# Single-ADC_ADS1252U.net
KiCad netlist of a schematic drawn in Altium Designer
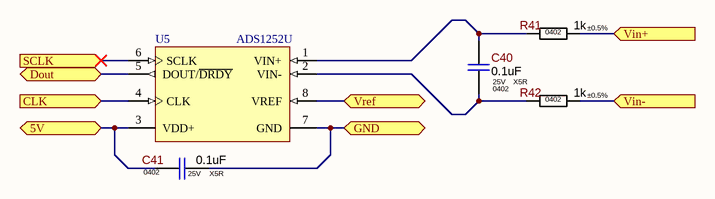
[diagram p0: Single-ADC_ADS1252U.SchDoc]

(export (version "E")
  (design (tool "Eeschema 10.0.6"))
  (components
    (comp (ref "C40")
      (value "0.1uF")
      (footprint "C_CERAMIC_0402_MED")
      (description "100nF 25V X5R ±10% 0402 Ceramic Capacitor RoHS")
      (fields
        (field (name "PART NUMBER") "CL05A104KA5NNNC")
        (field (name "MANUFACTURER") "Samsung Electro-Mechanics")
        (field (name "PACKAGE") "0402")
        (field (name "VOLTAGE") "25V")
        (field (name "DIELECTRIC TYPE") "X5R")
      )
      (libsource (lib "EL.XXX.T01") (part "CL05A104KA5NNNC"))
    )
    (comp (ref "C41")
      (value "0.1uF")
      (footprint "C_CERAMIC_0402_HI")
      (description "100nF 25V X5R ±10% 0402 Ceramic Capacitor RoHS")
      (fields
        (field (name "PACKAGE") "0402")
        (field (name "VOLTAGE") "25V")
        (field (name "DIELECTRIC TYPE") "X5R")
        (field (name "PART NUMBER") "CL05A104KA5NNNC")
        (field (name "MANUFACTURER") "Samsung Electro-Mechanics")
      )
      (libsource (lib "EL.XXX.T01") (part "CL05A104KA5NNNC"))
    )
    (comp (ref "R41")
      (value "1k")
      (footprint "R_ANY_CHIP_0402_HI")
      (description "1 kOhms ±0.5% 1/16W 0402 Thick Film Resistor")
      (fields
        (field (name "PART NUMBER") "RC0402DR-071KL")
        (field (name "MANUFACTURER") "Yageo")
        (field (name "TOLERANCE") "±0.5%")
        (field (name "PACKAGE") "0402")
      )
      (libsource (lib "EL.XXX.T01") (part "RC0402DR-071KL"))
    )
    (comp (ref "R42")
      (value "1k")
      (footprint "R_ANY_CHIP_0402_HI")
      (description "1 kOhms ±0.5% 1/16W 0402 Thick Film Resistor")
      (fields
        (field (name "PART NUMBER") "RC0402DR-071KL")
        (field (name "MANUFACTURER") "Yageo")
        (field (name "TOLERANCE") "±0.5%")
        (field (name "PACKAGE") "0402")
      )
      (libsource (lib "EL.XXX.T01") (part "RC0402DR-071KL"))
    )
    (comp (ref "U5")
      (value "ADS1252U")
      (footprint "TI-D8_M")
      (description "ResolutionPlus 24-Bit, 40 kHz ADC, -40 to 85 degC, 8-pin SOIC (D8), Green (RoHS & no Sb/Br)")
      (fields (field (name "MANUFACTURER") "Texas Instruments"))
      (libsource (lib "EL.XXX.T01") (part "CMP-0003-00072-2"))
    )
  )
  (nets
    (net (code "1") (name "/5V") (class "Default")
      (node (ref "C41") (pin "1") (pinfunction "1_1") (pintype "passive"))
      (node (ref "U5") (pin "3") (pinfunction "VDD+_3") (pintype "power_in"))
    )
    (net (code "2") (name "/CLK") (class "Default")
      (node (ref "U5") (pin "4") (pinfunction "CLK_4") (pintype "input"))
    )
    (net (code "3") (name "/Dout") (class "Default")
      (node (ref "U5") (pin "5") (pinfunction "DOUT/~{DRDY}_5") (pintype "output"))
    )
    (net (code "4") (name "/GND") (class "Default")
      (node (ref "C41") (pin "2") (pinfunction "2_2") (pintype "passive"))
      (node (ref "U5") (pin "7") (pinfunction "GND_7") (pintype "power_in"))
    )
    (net (code "5") (name "/SCLK") (class "Default")
      (node (ref "U5") (pin "6") (pinfunction "SCLK_6") (pintype "input+no_connect"))
    )
    (net (code "6") (name "/Vin+") (class "Default") (node (ref "R41") (pin "1") (pintype "passive")))
    (net (code "7") (name "/Vin-") (class "Default") (node (ref "R42") (pin "1") (pintype "passive")))
    (net (code "8") (name "/Vref") (class "Default")
      (node (ref "U5") (pin "8") (pinfunction "VREF_8") (pintype "input"))
    )
    (net (code "9") (name "Net-(U5-VIN+)") (class "Default")
      (node (ref "C40") (pin "1") (pinfunction "1_1") (pintype "passive"))
      (node (ref "R41") (pin "2") (pintype "passive"))
      (node (ref "U5") (pin "1") (pinfunction "VIN+_1") (pintype "input"))
    )
    (net (code "10") (name "Net-(U5-VIN-)") (class "Default")
      (node (ref "C40") (pin "2") (pinfunction "2_2") (pintype "passive"))
      (node (ref "R42") (pin "2") (pintype "passive"))
      (node (ref "U5") (pin "2") (pinfunction "VIN-_2") (pintype "input"))
    )
  )
)
